# SLAVE.net
KiCad netlist of a schematic drawn in Altium Designer
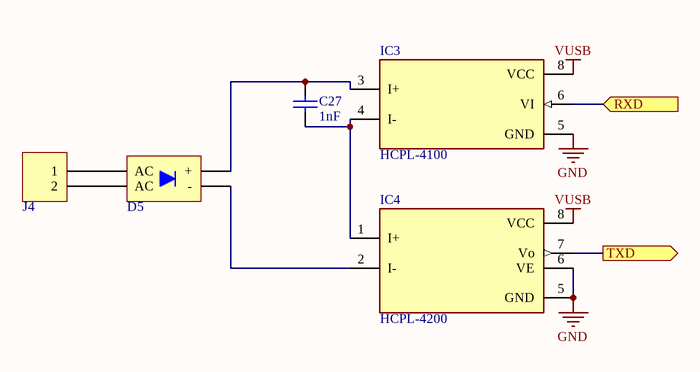
[diagram p0: SLAVE.SchDoc]

(export (version "E")
  (design (tool "Eeschema 10.0.6"))
  (components
    (comp (ref "C27")
      (value "1nF")
      (footprint "PARSALIBRARY:C1206")
      (description "Capacitor")
      (fields (field (name "DESIGNER") "Parsa Malekpour"))
      (libsource (lib "ParsaLibrary") (part "Cap"))
    )
    (comp (ref "D5") (value "HD08") (footprint "MINIDIP") (libsource (lib "ParsaLibrary") (part "HD08")))
    (comp (ref "IC3")
      (value "HCPL-4100")
      (footprint "PARSALIBRARY:DIP-8")
      (description "<b>Isolation Amplifer</b><p> Source: http://www.avagotech.com/docs/AV02-0410EN")
      (fields (field (name "MF") "{'manufacturer': u'Broadcom Limited'}"))
      (libsource (lib "ParsaLibrary") (part "HCPL-4100"))
    )
    (comp (ref "IC4")
      (value "HCPL-4200")
      (footprint "PARSALIBRARY:DIP-8")
      (description "Optically Coupled 20 mA Current Loop Receiver")
      (fields (field (name "MF") "{'manufacturer': u'Broadcom Limited'}") (field (name "MP") "HCPL-4100"))
      (libsource (lib "ParsaLibrary") (part "HCPL-4200"))
    )
    (comp (ref "J4") (value "CONN-2") (footprint "XH-2") (libsource (lib "ParsaLibrary") (part "CONN-2")))
  )
  (nets
    (net (code "1") (name "/RXD") (class "Default")
      (node (ref "IC3") (pin "6") (pinfunction "VI_6") (pintype "input"))
    )
    (net (code "2") (name "/TXD") (class "Default")
      (node (ref "IC4") (pin "7") (pinfunction "Vo_7") (pintype "output"))
    )
    (net (code "3") (name "GND") (class "Default")
      (node (ref "IC3") (pin "5") (pinfunction "GND_5") (pintype "power_in"))
      (node (ref "IC4") (pin "5") (pinfunction "GND_5") (pintype "power_in"))
      (node (ref "IC4") (pin "6") (pinfunction "VE_6") (pintype "power_in"))
    )
    (net (code "4") (name "Net-(D5-+)") (class "Default")
      (node (ref "C27") (pin "2") (pinfunction "2_2") (pintype "passive"))
      (node (ref "D5") (pin "1") (pinfunction "+_1") (pintype "passive"))
      (node (ref "IC3") (pin "3") (pinfunction "I+_3") (pintype "power_in"))
    )
    (net (code "5") (name "Net-(D5--)") (class "Default")
      (node (ref "D5") (pin "2") (pinfunction "-_2") (pintype "passive"))
      (node (ref "IC4") (pin "2") (pinfunction "I-_2") (pintype "power_in"))
    )
    (net (code "6") (name "Net-(D5-AC-Pad3)") (class "Default")
      (node (ref "D5") (pin "3") (pinfunction "AC_3") (pintype "passive"))
      (node (ref "J4") (pin "2") (pinfunction "2_2") (pintype "passive"))
    )
    (net (code "7") (name "Net-(D5-AC-Pad4)") (class "Default")
      (node (ref "D5") (pin "4") (pinfunction "AC_4") (pintype "passive"))
      (node (ref "J4") (pin "1") (pinfunction "1_1") (pintype "passive"))
    )
    (net (code "8") (name "Net-(IC3-I-)") (class "Default")
      (node (ref "C27") (pin "1") (pinfunction "1_1") (pintype "passive"))
      (node (ref "IC3") (pin "4") (pinfunction "I-_4") (pintype "power_in"))
      (node (ref "IC4") (pin "1") (pinfunction "I+_1") (pintype "power_in"))
    )
    (net (code "9") (name "VUSB") (class "Default")
      (node (ref "IC3") (pin "8") (pinfunction "VCC_8") (pintype "power_in"))
      (node (ref "IC4") (pin "8") (pinfunction "VCC_8") (pintype "power_in"))
    )
  )
)
